# 01_-_BMS.net
KiCad netlist of a schematic drawn in Altium Designer
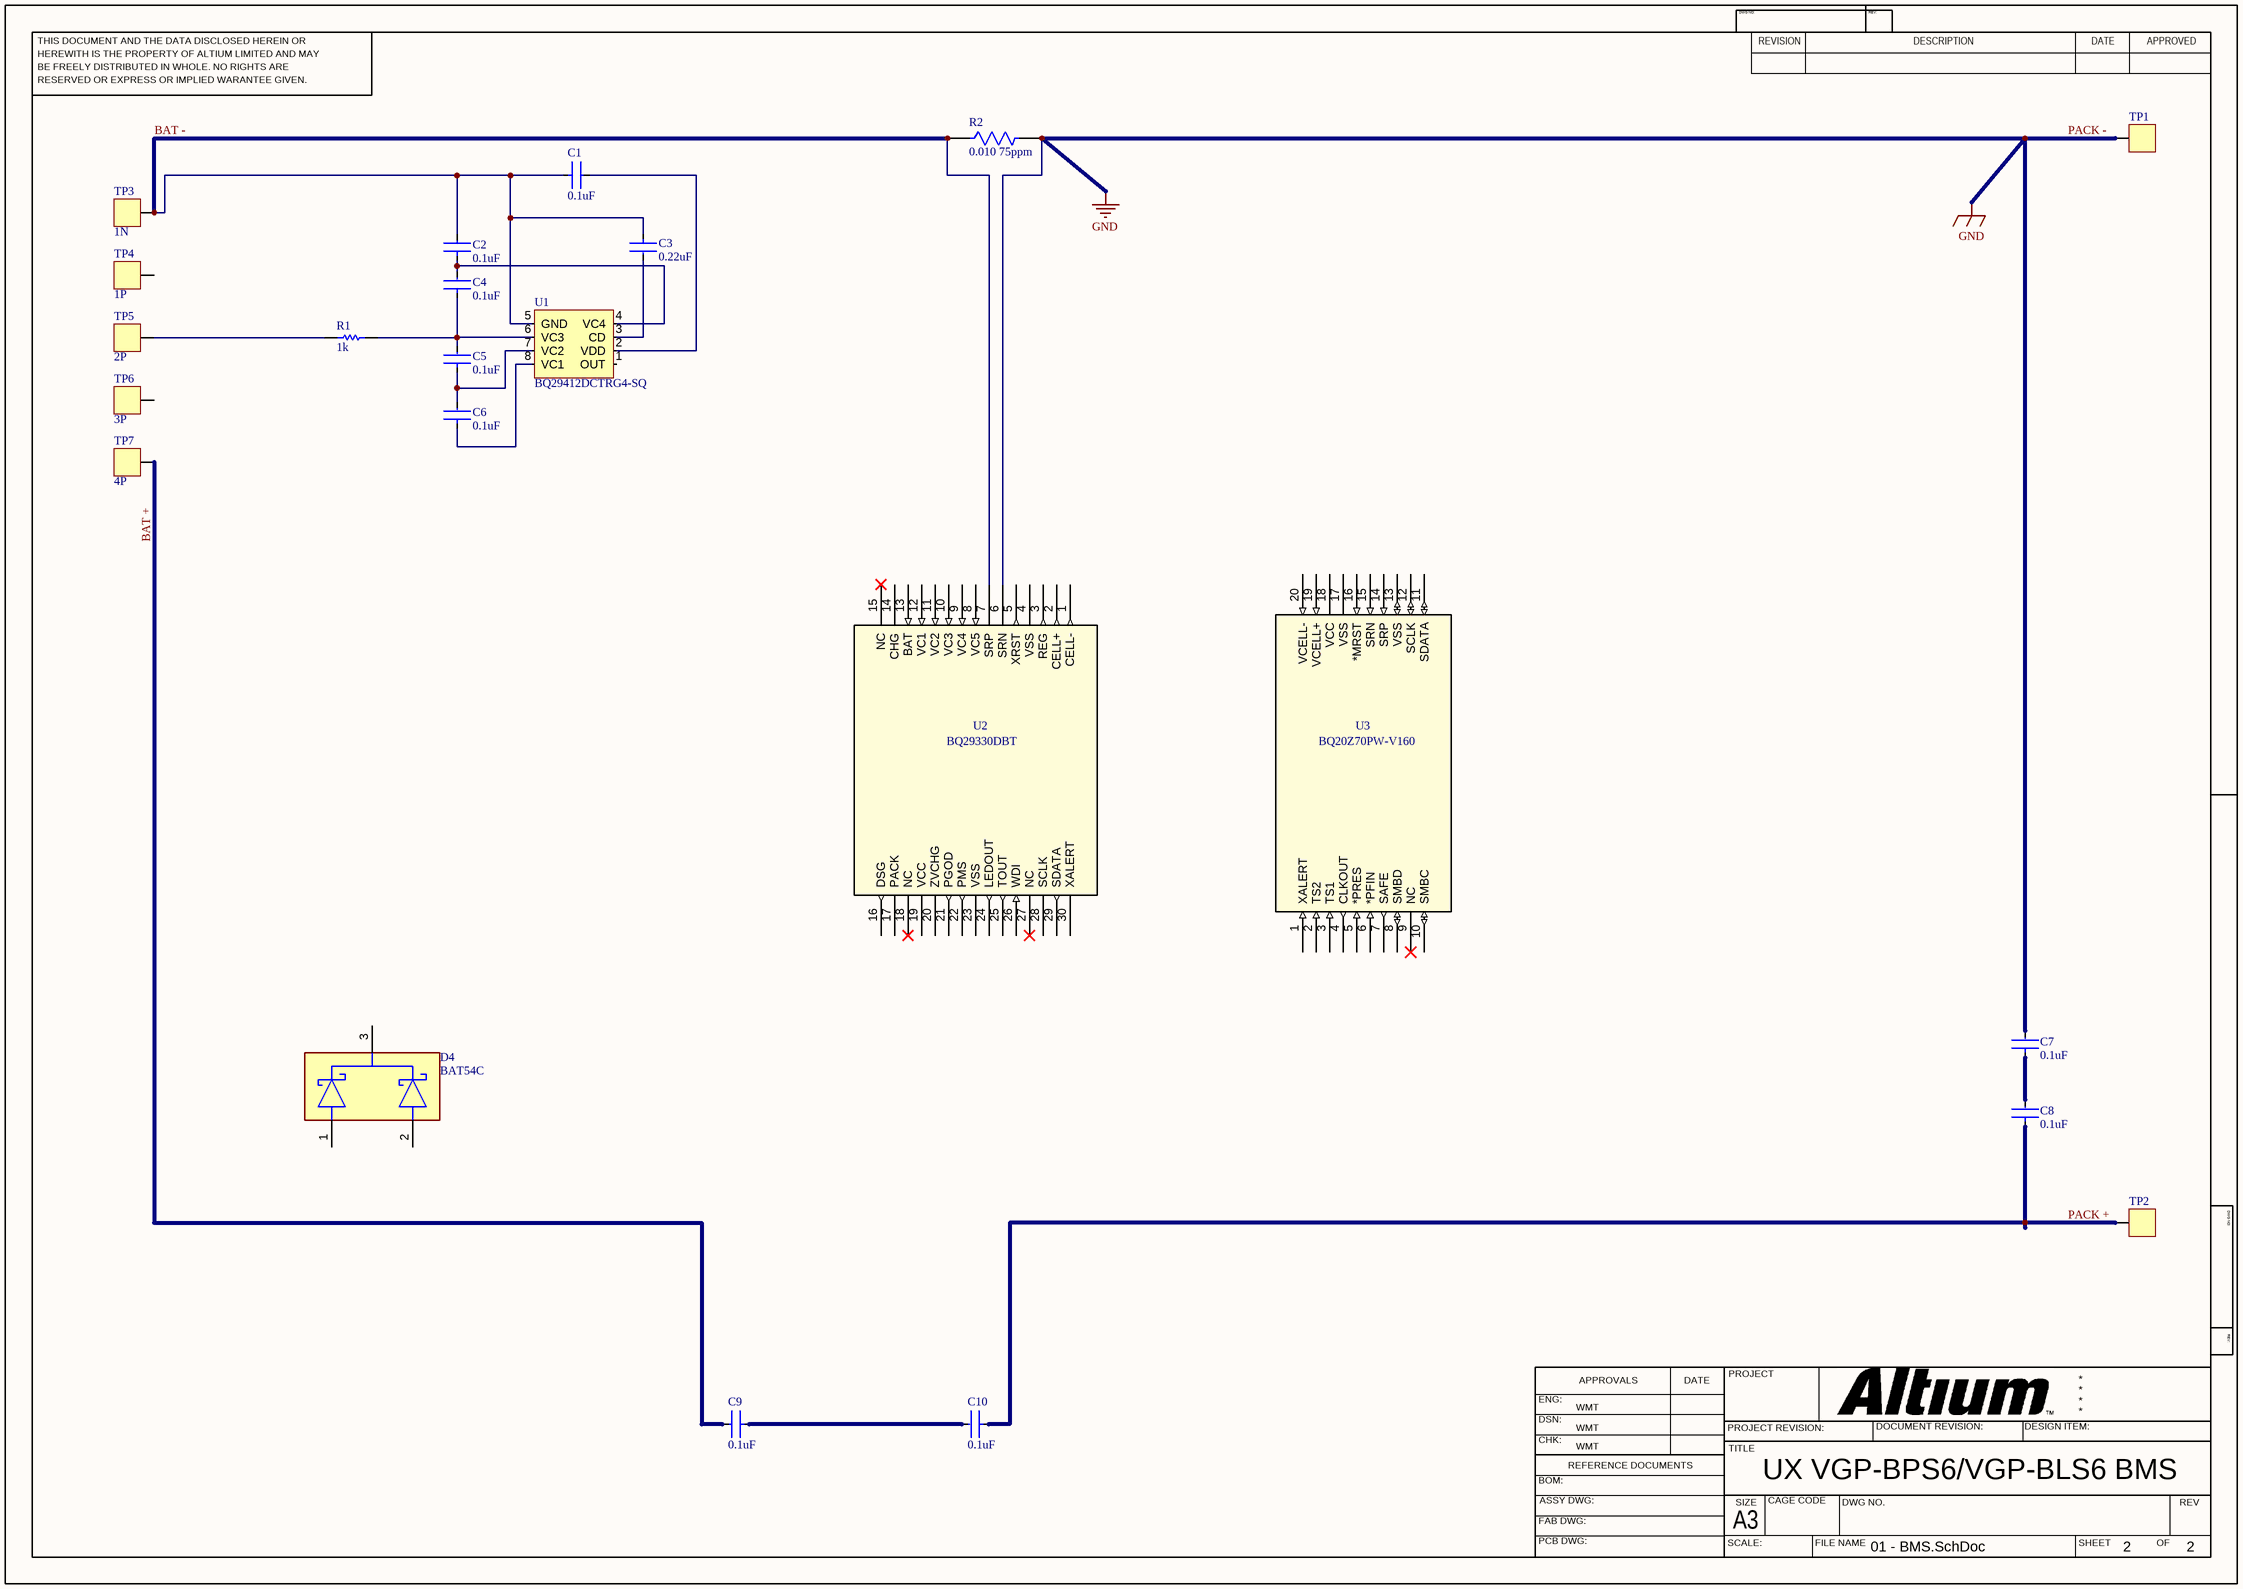
[diagram p0: 01 - BMS.SchDoc]

(export (version "E")
  (design (tool "Eeschema 10.0.6"))
  (components
    (comp (ref "C1")
      (value "0.1uF")
      (footprint "FP-GRM033-0_03-IPC_C")
      (description "Chip Multilayer Ceramic Capacitors for General Purpose, 0201, 0.10uF, X5R, 15%, 10%, 10V")
      (fields (field (name "TOLERANCE") "10%") (field (name "VOLTAGE") "10V"))
      (libsource (lib "Altium Content Vault") (part "b4654b650e69147ec39a6b967a45e02"))
    )
    (comp (ref "C2")
      (value "0.1uF")
      (footprint "FP-GRM033-0_03-IPC_C")
      (description "Chip Multilayer Ceramic Capacitors for General Purpose, 0201, 0.10uF, X5R, 15%, 10%, 10V")
      (fields (field (name "TOLERANCE") "10%") (field (name "VOLTAGE") "10V"))
      (libsource (lib "Altium Content Vault") (part "b4654b650e69147ec39a6b967a45e02"))
    )
    (comp (ref "C3")
      (value "0.22uF")
      (footprint "FP-CL03-IPC_C")
      (description "Cap Ceramic 220nF 10V X5R ±10% Pad SMD 0201 +85°C T/R")
      (fields (field (name "TOLERANCE") "10%"))
      (libsource (lib "Altium Content Vault") (part "b4654b650e69147ec39a6b967a45e02"))
    )
    (comp (ref "C4")
      (value "0.1uF")
      (footprint "FP-GRM033-0_03-IPC_C")
      (description "Chip Multilayer Ceramic Capacitors for General Purpose, 0201, 0.10uF, X5R, 15%, 10%, 10V")
      (fields (field (name "TOLERANCE") "10%") (field (name "VOLTAGE") "10V"))
      (libsource (lib "Altium Content Vault") (part "b4654b650e69147ec39a6b967a45e02"))
    )
    (comp (ref "C5")
      (value "0.1uF")
      (footprint "FP-GRM033-0_03-IPC_C")
      (description "Chip Multilayer Ceramic Capacitors for General Purpose, 0201, 0.10uF, X5R, 15%, 10%, 10V")
      (fields (field (name "TOLERANCE") "10%") (field (name "VOLTAGE") "10V"))
      (libsource (lib "Altium Content Vault") (part "b4654b650e69147ec39a6b967a45e02"))
    )
    (comp (ref "C6")
      (value "0.1uF")
      (footprint "FP-GRM033-0_03-IPC_C")
      (description "Chip Multilayer Ceramic Capacitors for General Purpose, 0201, 0.10uF, X5R, 15%, 10%, 10V")
      (fields (field (name "TOLERANCE") "10%") (field (name "VOLTAGE") "10V"))
      (libsource (lib "Altium Content Vault") (part "b4654b650e69147ec39a6b967a45e02"))
    )
    (comp (ref "C7")
      (value "0.1uF")
      (footprint "FP-GRM033-0_03-IPC_C")
      (description "Chip Multilayer Ceramic Capacitors for General Purpose, 0201, 0.10uF, X5R, 15%, 10%, 10V")
      (fields (field (name "TOLERANCE") "10%") (field (name "VOLTAGE") "10V"))
      (libsource (lib "Altium Content Vault") (part "b4654b650e69147ec39a6b967a45e02"))
    )
    (comp (ref "C8")
      (value "0.1uF")
      (footprint "FP-GRM033-0_03-IPC_C")
      (description "Chip Multilayer Ceramic Capacitors for General Purpose, 0201, 0.10uF, X5R, 15%, 10%, 10V")
      (fields (field (name "TOLERANCE") "10%") (field (name "VOLTAGE") "10V"))
      (libsource (lib "Altium Content Vault") (part "b4654b650e69147ec39a6b967a45e02"))
    )
    (comp (ref "C9")
      (value "0.1uF")
      (footprint "FP-GRM033-0_03-IPC_C")
      (description "Chip Multilayer Ceramic Capacitors for General Purpose, 0201, 0.10uF, X5R, 15%, 10%, 10V")
      (fields (field (name "TOLERANCE") "10%") (field (name "VOLTAGE") "10V"))
      (libsource (lib "Altium Content Vault") (part "b4654b650e69147ec39a6b967a45e02"))
    )
    (comp (ref "C10")
      (value "0.1uF")
      (footprint "FP-GRM033-0_03-IPC_C")
      (description "Chip Multilayer Ceramic Capacitors for General Purpose, 0201, 0.10uF, X5R, 15%, 10%, 10V")
      (fields (field (name "TOLERANCE") "10%") (field (name "VOLTAGE") "10V"))
      (libsource (lib "Altium Content Vault") (part "b4654b650e69147ec39a6b967a45e02"))
    )
    (comp (ref "D4")
      (value "BAT54C")
      (footprint "FP-MA03D-MFG")
      (description "DIODE ARRAY SCHOTTKY 30V SOT23-3")
      (fields
        (field (name "OBSOLETE PART") "true")
        (field (name "OCTOPART") "https://octopart.com/bat54c-on+semiconductor-8095621")
      )
      (libsource (lib "Altium Content Vault") (part "a990b5859d77eb53ee18a746427302e"))
    )
    (comp (ref "R1")
      (value "1k")
      (footprint "RESC0603X26X15LL03T05")
      (fields
        (field (name "MANUFACTURER") "TE Connectivity / AMP")
        (field (name "PART NUMBER") "CRG0201F1K0")
      )
      (libsource (lib "Altium Content Vault") (part "RES"))
    )
    (comp (ref "R2")
      (value "0.010 75ppm")
      (footprint "FP-ERJ8CW-MFG")
      (description "RES 0.01 OHM 1% 1W 1206")
      (fields (field (name "TOLERANCE") "1%"))
      (libsource (lib "Altium Content Vault") (part "1029c3af85768c4190bb7ad29bc67b5"))
    )
    (comp (ref "TP1")
      (value "Pad")
      (footprint "PAD_SQ_2MM")
      (description "Test Point Square 2mm")
      (libsource (lib "") (part "PAD_SQ_2MM_1"))
    )
    (comp (ref "TP2")
      (value "Pad")
      (footprint "PAD_SQ_2MM")
      (description "Test Point Square 2mm")
      (libsource (lib "") (part "PAD_SQ_2MM_1"))
    )
    (comp (ref "TP3")
      (value "1N")
      (footprint "PAD_SQ_2MM")
      (description "Test Point Square 2mm")
      (libsource (lib "Custom Schematic Library") (part "PAD_SQ_2MM"))
    )
    (comp (ref "TP4")
      (value "1P")
      (footprint "PAD_SQ_2MM")
      (description "Test Point Square 2mm")
      (libsource (lib "Custom Schematic Library") (part "PAD_SQ_2MM"))
    )
    (comp (ref "TP5")
      (value "2P")
      (footprint "PAD_SQ_2MM")
      (description "Test Point Square 2mm")
      (libsource (lib "Custom Schematic Library") (part "PAD_SQ_2MM"))
    )
    (comp (ref "TP6")
      (value "3P")
      (footprint "PAD_SQ_2MM")
      (description "Test Point Square 2mm")
      (libsource (lib "Custom Schematic Library") (part "PAD_SQ_2MM"))
    )
    (comp (ref "TP7")
      (value "4P")
      (footprint "PAD_SQ_2MM")
      (description "Test Point Square 2mm")
      (libsource (lib "Custom Schematic Library") (part "PAD_SQ_2MM"))
    )
    (comp (ref "U1")
      (value "BQ29412DCTRG4-SQ")
      (footprint "DCT8")
      (libsource (lib "BQ29412DCTRG4") (part "BQ29412DCTRG4-SQ"))
    )
    (comp (ref "U2")
      (value "BQ29330DBT")
      (footprint "DBT30")
      (description "No Description Available")
      (libsource (lib "BQ29330DBT") (part "BQ29330DBT"))
    )
    (comp (ref "U3")
      (value "BQ20Z70PW-V160")
      (footprint "PW20")
      (description "No Description Available")
      (libsource (lib "BQ20Z70PW-V160") (part "BQ20Z70PW-V160"))
    )
  )
  (nets
    (net (code "1") (name "/BAT +") (class "Default")
      (node (ref "C9") (pin "2") (pinfunction "2_2") (pintype "passive"))
      (node (ref "TP7") (pin "1") (pinfunction "1_1") (pintype "passive"))
    )
    (net (code "2") (name "/BAT -") (class "Default")
      (node (ref "C1") (pin "1") (pinfunction "1_1") (pintype "passive"))
      (node (ref "C2") (pin "2") (pinfunction "2_2") (pintype "passive"))
      (node (ref "C3") (pin "1") (pinfunction "1_1") (pintype "passive"))
      (node (ref "R2") (pin "1") (pinfunction "1_1") (pintype "passive"))
      (node (ref "TP3") (pin "1") (pinfunction "1_1") (pintype "passive"))
      (node (ref "U1") (pin "5") (pinfunction "GND_5") (pintype "power_in"))
      (node (ref "U2") (pin "7") (pinfunction "SRP_7") (pintype "passive"))
    )
    (net (code "3") (name "/PACK +") (class "Default")
      (node (ref "C10") (pin "1") (pinfunction "1_1") (pintype "passive"))
      (node (ref "C8") (pin "1") (pinfunction "1_1") (pintype "passive"))
      (node (ref "TP2") (pin "1") (pinfunction "1_1") (pintype "passive"))
    )
    (net (code "4") (name "GND") (class "Default")
      (node (ref "C7") (pin "2") (pinfunction "2_2") (pintype "passive"))
      (node (ref "R2") (pin "2") (pinfunction "2_2") (pintype "passive"))
      (node (ref "TP1") (pin "1") (pinfunction "1_1") (pintype "passive"))
      (node (ref "U2") (pin "6") (pinfunction "SRN_6") (pintype "passive"))
    )
    (net (code "5") (name "Net-(C7-Pad1)") (class "Default")
      (node (ref "C7") (pin "1") (pinfunction "1_1") (pintype "passive"))
      (node (ref "C8") (pin "2") (pinfunction "2_2") (pintype "passive"))
    )
    (net (code "6") (name "Net-(C10-Pad2)") (class "Default")
      (node (ref "C10") (pin "2") (pinfunction "2_2") (pintype "passive"))
      (node (ref "C9") (pin "1") (pinfunction "1_1") (pintype "passive"))
    )
    (net (code "7") (name "Net-(R1-Pad1)") (class "Default")
      (node (ref "R1") (pin "1") (pinfunction "1_1") (pintype "passive"))
      (node (ref "TP5") (pin "1") (pinfunction "1_1") (pintype "passive"))
    )
    (net (code "8") (name "Net-(U1-CD)") (class "Default")
      (node (ref "C3") (pin "2") (pinfunction "2_2") (pintype "passive"))
      (node (ref "U1") (pin "3") (pinfunction "CD_3") (pintype "passive"))
    )
    (net (code "9") (name "Net-(U1-VC1)") (class "Default")
      (node (ref "C6") (pin "1") (pinfunction "1_1") (pintype "passive"))
      (node (ref "U1") (pin "8") (pinfunction "VC1_8") (pintype "input"))
    )
    (net (code "10") (name "Net-(U1-VC2)") (class "Default")
      (node (ref "C5") (pin "1") (pinfunction "1_1") (pintype "passive"))
      (node (ref "C6") (pin "2") (pinfunction "2_2") (pintype "passive"))
      (node (ref "U1") (pin "7") (pinfunction "VC2_7") (pintype "input"))
    )
    (net (code "11") (name "Net-(U1-VC3)") (class "Default")
      (node (ref "C4") (pin "1") (pinfunction "1_1") (pintype "passive"))
      (node (ref "C5") (pin "2") (pinfunction "2_2") (pintype "passive"))
      (node (ref "R1") (pin "2") (pinfunction "2_2") (pintype "passive"))
      (node (ref "U1") (pin "6") (pinfunction "VC3_6") (pintype "input"))
    )
    (net (code "12") (name "Net-(U1-VC4)") (class "Default")
      (node (ref "C2") (pin "1") (pinfunction "1_1") (pintype "passive"))
      (node (ref "C4") (pin "2") (pinfunction "2_2") (pintype "passive"))
      (node (ref "U1") (pin "4") (pinfunction "VC4_4") (pintype "input"))
    )
    (net (code "13") (name "Net-(U1-VDD)") (class "Default")
      (node (ref "C1") (pin "2") (pinfunction "2_2") (pintype "passive"))
      (node (ref "U1") (pin "2") (pinfunction "VDD_2") (pintype "power_in"))
    )
    (net (code "14") (name "unconnected-(D4-1_ANODE-Pad1)") (class "Default")
      (node (ref "D4") (pin "1") (pinfunction "1_ANODE_1") (pintype "passive"))
    )
    (net (code "15") (name "unconnected-(D4-2_ANODE-Pad2)") (class "Default")
      (node (ref "D4") (pin "2") (pinfunction "2_ANODE_2") (pintype "passive"))
    )
    (net (code "16") (name "unconnected-(D4-COMMON_CATHODE-Pad3)") (class "Default")
      (node (ref "D4") (pin "3") (pinfunction "COMMON_CATHODE_3") (pintype "passive"))
    )
    (net (code "17") (name "unconnected-(TP4-Pad1)") (class "Default")
      (node (ref "TP4") (pin "1") (pinfunction "1_1") (pintype "passive"))
    )
    (net (code "18") (name "unconnected-(TP6-Pad1)") (class "Default")
      (node (ref "TP6") (pin "1") (pinfunction "1_1") (pintype "passive"))
    )
    (net (code "19") (name "unconnected-(U1-OUT-Pad1)") (class "Default")
      (node (ref "U1") (pin "1") (pinfunction "OUT_1") (pintype "output"))
    )
    (net (code "20") (name "unconnected-(U2-BAT-Pad13)") (class "Default")
      (node (ref "U2") (pin "13") (pinfunction "BAT_13") (pintype "input"))
    )
    (net (code "21") (name "unconnected-(U2-CELL+-Pad2)") (class "Default")
      (node (ref "U2") (pin "2") (pinfunction "CELL+_2") (pintype "output"))
    )
    (net (code "22") (name "unconnected-(U2-CELL--Pad1)") (class "Default")
      (node (ref "U2") (pin "1") (pinfunction "CELL-_1") (pintype "output"))
    )
    (net (code "23") (name "unconnected-(U2-CHG-Pad14)") (class "Default")
      (node (ref "U2") (pin "14") (pinfunction "CHG_14") (pintype "passive"))
    )
    (net (code "24") (name "unconnected-(U2-DSG-Pad16)") (class "Default")
      (node (ref "U2") (pin "16") (pinfunction "DSG_16") (pintype "output"))
    )
    (net (code "25") (name "unconnected-(U2-LEDOUT-Pad24)") (class "Default")
      (node (ref "U2") (pin "24") (pinfunction "LEDOUT_24") (pintype "output"))
    )
    (net (code "26") (name "unconnected-(U2-NC-Pad15)") (class "Default")
      (node (ref "U2") (pin "15") (pinfunction "NC_15") (pintype "passive+no_connect"))
    )
    (net (code "27") (name "unconnected-(U2-NC-Pad18)") (class "Default")
      (node (ref "U2") (pin "18") (pinfunction "NC_18") (pintype "passive+no_connect"))
    )
    (net (code "28") (name "unconnected-(U2-NC-Pad27)") (class "Default")
      (node (ref "U2") (pin "27") (pinfunction "NC_27") (pintype "passive+no_connect"))
    )
    (net (code "29") (name "unconnected-(U2-PACK-Pad17)") (class "Default")
      (node (ref "U2") (pin "17") (pinfunction "PACK_17") (pintype "passive"))
    )
    (net (code "30") (name "unconnected-(U2-PGOD-Pad21)") (class "Default")
      (node (ref "U2") (pin "21") (pinfunction "PGOD_21") (pintype "output"))
    )
    (net (code "31") (name "unconnected-(U2-PMS-Pad22)") (class "Default")
      (node (ref "U2") (pin "22") (pinfunction "PMS_22") (pintype "output"))
    )
    (net (code "32") (name "unconnected-(U2-REG-Pad3)") (class "Default")
      (node (ref "U2") (pin "3") (pinfunction "REG_3") (pintype "output"))
    )
    (net (code "33") (name "unconnected-(U2-SCLK-Pad28)") (class "Default")
      (node (ref "U2") (pin "28") (pinfunction "SCLK_28") (pintype "passive"))
    )
    (net (code "34") (name "unconnected-(U2-SDATA-Pad29)") (class "Default")
      (node (ref "U2") (pin "29") (pinfunction "SDATA_29") (pintype "output"))
    )
    (net (code "35") (name "unconnected-(U2-TOUT-Pad25)") (class "Default")
      (node (ref "U2") (pin "25") (pinfunction "TOUT_25") (pintype "output"))
    )
    (net (code "36") (name "unconnected-(U2-VC1-Pad12)") (class "Default")
      (node (ref "U2") (pin "12") (pinfunction "VC1_12") (pintype "input"))
    )
    (net (code "37") (name "unconnected-(U2-VC2-Pad11)") (class "Default")
      (node (ref "U2") (pin "11") (pinfunction "VC2_11") (pintype "input"))
    )
    (net (code "38") (name "unconnected-(U2-VC3-Pad10)") (class "Default")
      (node (ref "U2") (pin "10") (pinfunction "VC3_10") (pintype "input"))
    )
    (net (code "39") (name "unconnected-(U2-VC4-Pad9)") (class "Default")
      (node (ref "U2") (pin "9") (pinfunction "VC4_9") (pintype "input"))
    )
    (net (code "40") (name "unconnected-(U2-VC5-Pad8)") (class "Default")
      (node (ref "U2") (pin "8") (pinfunction "VC5_8") (pintype "input"))
    )
    (net (code "41") (name "unconnected-(U2-VCC-Pad19)") (class "Default")
      (node (ref "U2") (pin "19") (pinfunction "VCC_19") (pintype "power_in"))
    )
    (net (code "42") (name "unconnected-(U2-VSS-Pad4)") (class "Default")
      (node (ref "U2") (pin "4") (pinfunction "VSS_4") (pintype "power_in"))
    )
    (net (code "43") (name "unconnected-(U2-VSS-Pad23)") (class "Default")
      (node (ref "U2") (pin "23") (pinfunction "VSS_23") (pintype "power_in"))
    )
    (net (code "44") (name "unconnected-(U2-WDI-Pad26)") (class "Default")
      (node (ref "U2") (pin "26") (pinfunction "WDI_26") (pintype "input"))
    )
    (net (code "45") (name "unconnected-(U2-XALERT-Pad30)") (class "Default")
      (node (ref "U2") (pin "30") (pinfunction "XALERT_30") (pintype "passive"))
    )
    (net (code "46") (name "unconnected-(U2-XRST-Pad5)") (class "Default")
      (node (ref "U2") (pin "5") (pinfunction "XRST_5") (pintype "output"))
    )
    (net (code "47") (name "unconnected-(U2-ZVCHG-Pad20)") (class "Default")
      (node (ref "U2") (pin "20") (pinfunction "ZVCHG_20") (pintype "passive"))
    )
    (net (code "48") (name "unconnected-(U3-*MRST-Pad16)") (class "Default")
      (node (ref "U3") (pin "16") (pinfunction "*MRST_16") (pintype "input"))
    )
    (net (code "49") (name "unconnected-(U3-*PFIN-Pad6)") (class "Default")
      (node (ref "U3") (pin "6") (pinfunction "*PFIN_6") (pintype "input"))
    )
    (net (code "50") (name "unconnected-(U3-*PRES-Pad5)") (class "Default")
      (node (ref "U3") (pin "5") (pinfunction "*PRES_5") (pintype "input"))
    )
    (net (code "51") (name "unconnected-(U3-CLKOUT-Pad4)") (class "Default")
      (node (ref "U3") (pin "4") (pinfunction "CLKOUT_4") (pintype "output"))
    )
    (net (code "52") (name "unconnected-(U3-NC-Pad9)") (class "Default")
      (node (ref "U3") (pin "9") (pinfunction "NC_9") (pintype "passive+no_connect"))
    )
    (net (code "53") (name "unconnected-(U3-SAFE-Pad7)") (class "Default")
      (node (ref "U3") (pin "7") (pinfunction "SAFE_7") (pintype "output"))
    )
    (net (code "54") (name "unconnected-(U3-SCLK-Pad12)") (class "Default")
      (node (ref "U3") (pin "12") (pinfunction "SCLK_12") (pintype "bidirectional"))
    )
    (net (code "55") (name "unconnected-(U3-SDATA-Pad11)") (class "Default")
      (node (ref "U3") (pin "11") (pinfunction "SDATA_11") (pintype "bidirectional"))
    )
    (net (code "56") (name "unconnected-(U3-SMBC-Pad10)") (class "Default")
      (node (ref "U3") (pin "10") (pinfunction "SMBC_10") (pintype "bidirectional"))
    )
    (net (code "57") (name "unconnected-(U3-SMBD-Pad8)") (class "Default")
      (node (ref "U3") (pin "8") (pinfunction "SMBD_8") (pintype "bidirectional"))
    )
    (net (code "58") (name "unconnected-(U3-SRN-Pad15)") (class "Default")
      (node (ref "U3") (pin "15") (pinfunction "SRN_15") (pintype "input"))
    )
    (net (code "59") (name "unconnected-(U3-SRP-Pad14)") (class "Default")
      (node (ref "U3") (pin "14") (pinfunction "SRP_14") (pintype "input"))
    )
    (net (code "60") (name "unconnected-(U3-TS1-Pad3)") (class "Default")
      (node (ref "U3") (pin "3") (pinfunction "TS1_3") (pintype "input"))
    )
    (net (code "61") (name "unconnected-(U3-TS2-Pad2)") (class "Default")
      (node (ref "U3") (pin "2") (pinfunction "TS2_2") (pintype "input"))
    )
    (net (code "62") (name "unconnected-(U3-VCC-Pad18)") (class "Default")
      (node (ref "U3") (pin "18") (pinfunction "VCC_18") (pintype "power_in"))
    )
    (net (code "63") (name "unconnected-(U3-VCELL+-Pad19)") (class "Default")
      (node (ref "U3") (pin "19") (pinfunction "VCELL+_19") (pintype "input"))
    )
    (net (code "64") (name "unconnected-(U3-VCELL--Pad20)") (class "Default")
      (node (ref "U3") (pin "20") (pinfunction "VCELL-_20") (pintype "input"))
    )
    (net (code "65") (name "unconnected-(U3-VSS-Pad13)") (class "Default")
      (node (ref "U3") (pin "13") (pinfunction "VSS_13") (pintype "bidirectional"))
    )
    (net (code "66") (name "unconnected-(U3-VSS-Pad17)") (class "Default")
      (node (ref "U3") (pin "17") (pinfunction "VSS_17") (pintype "power_in"))
    )
    (net (code "67") (name "unconnected-(U3-XALERT-Pad1)") (class "Default")
      (node (ref "U3") (pin "1") (pinfunction "XALERT_1") (pintype "input"))
    )
  )
)
